# Belichter-Platinen.net
KiCad netlist of a schematic drawn in EAGLE
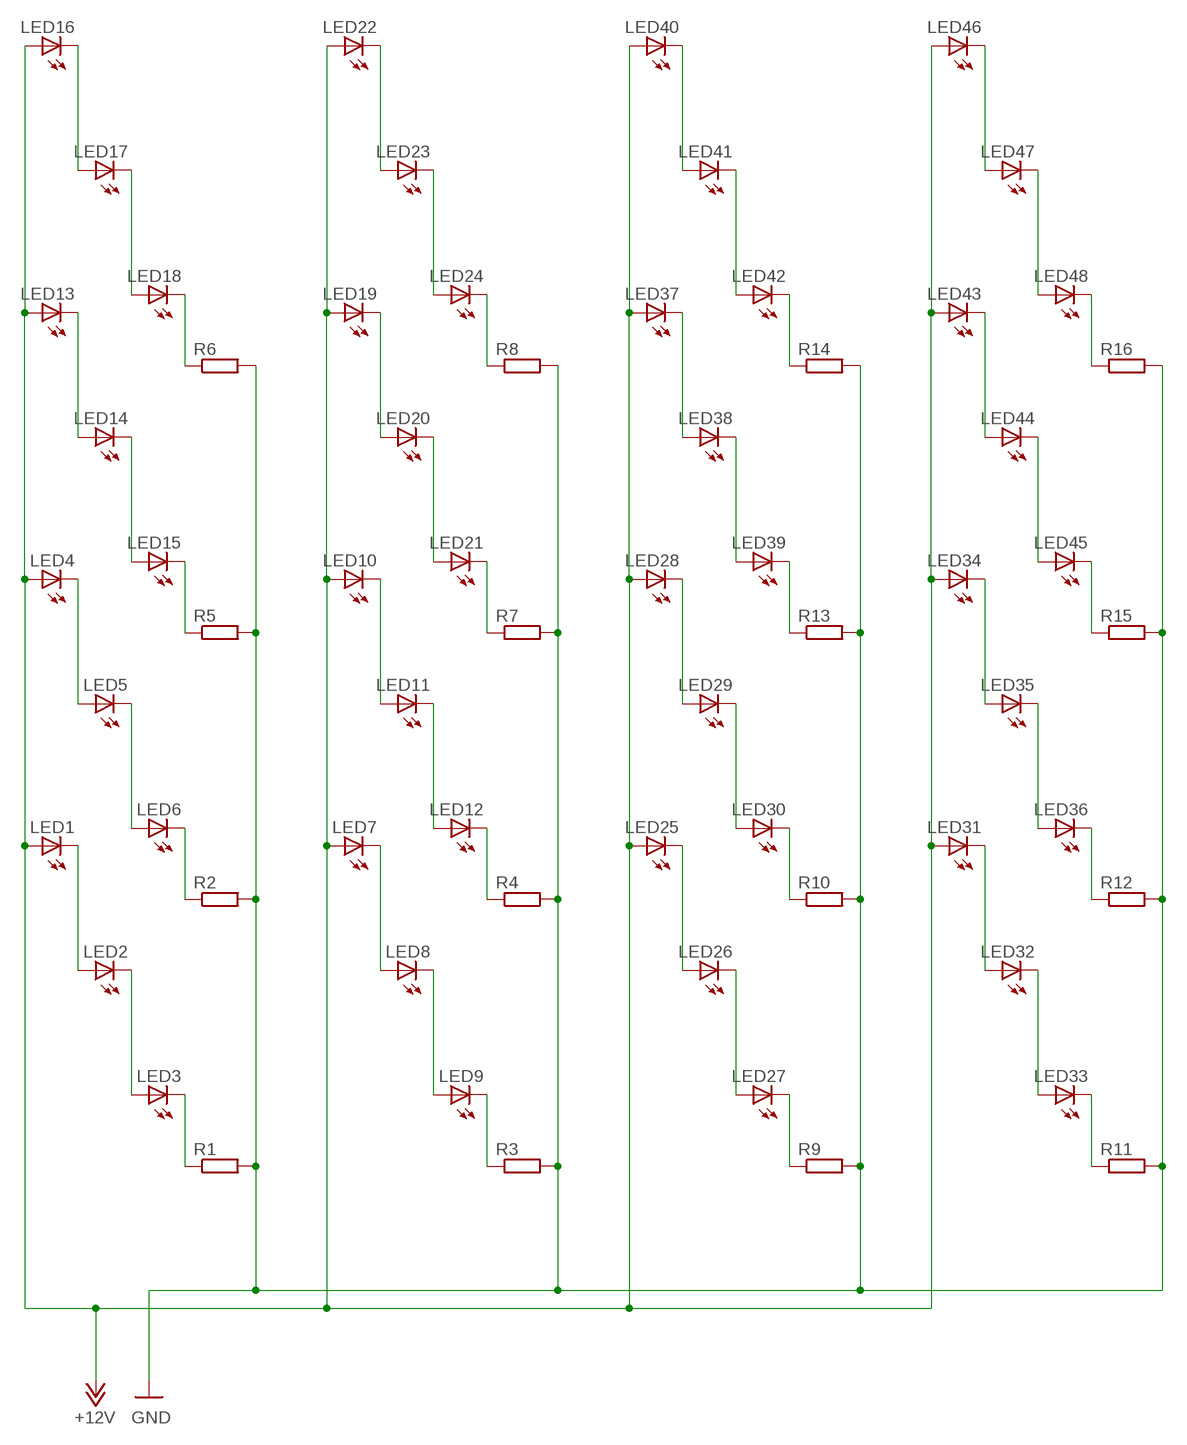
[diagram p0: schematic, sheet 1]

(export (version "E")
  (design (tool "Eeschema 10.0.6"))
  (components
    (comp (ref "LED1")
      (value "LED5MM")
      (footprint "eagle-import:LED5MM")
      (libsource (lib "eagle-import") (part "LED5MM"))
    )
    (comp (ref "LED2")
      (value "LED5MM")
      (footprint "eagle-import:LED5MM")
      (libsource (lib "eagle-import") (part "LED5MM"))
    )
    (comp (ref "LED3")
      (value "LED5MM")
      (footprint "eagle-import:LED5MM")
      (libsource (lib "eagle-import") (part "LED5MM"))
    )
    (comp (ref "LED4")
      (value "LED5MM")
      (footprint "eagle-import:LED5MM")
      (libsource (lib "eagle-import") (part "LED5MM"))
    )
    (comp (ref "LED5")
      (value "LED5MM")
      (footprint "eagle-import:LED5MM")
      (libsource (lib "eagle-import") (part "LED5MM"))
    )
    (comp (ref "LED6")
      (value "LED5MM")
      (footprint "eagle-import:LED5MM")
      (libsource (lib "eagle-import") (part "LED5MM"))
    )
    (comp (ref "LED7")
      (value "LED5MM")
      (footprint "eagle-import:LED5MM")
      (libsource (lib "eagle-import") (part "LED5MM"))
    )
    (comp (ref "LED8")
      (value "LED5MM")
      (footprint "eagle-import:LED5MM")
      (libsource (lib "eagle-import") (part "LED5MM"))
    )
    (comp (ref "LED9")
      (value "LED5MM")
      (footprint "eagle-import:LED5MM")
      (libsource (lib "eagle-import") (part "LED5MM"))
    )
    (comp (ref "LED10")
      (value "LED5MM")
      (footprint "eagle-import:LED5MM")
      (libsource (lib "eagle-import") (part "LED5MM"))
    )
    (comp (ref "LED11")
      (value "LED5MM")
      (footprint "eagle-import:LED5MM")
      (libsource (lib "eagle-import") (part "LED5MM"))
    )
    (comp (ref "LED12")
      (value "LED5MM")
      (footprint "eagle-import:LED5MM")
      (libsource (lib "eagle-import") (part "LED5MM"))
    )
    (comp (ref "LED13")
      (value "LED5MM")
      (footprint "eagle-import:LED5MM")
      (libsource (lib "eagle-import") (part "LED5MM"))
    )
    (comp (ref "LED14")
      (value "LED5MM")
      (footprint "eagle-import:LED5MM")
      (libsource (lib "eagle-import") (part "LED5MM"))
    )
    (comp (ref "LED15")
      (value "LED5MM")
      (footprint "eagle-import:LED5MM")
      (libsource (lib "eagle-import") (part "LED5MM"))
    )
    (comp (ref "LED16")
      (value "LED5MM")
      (footprint "eagle-import:LED5MM")
      (libsource (lib "eagle-import") (part "LED5MM"))
    )
    (comp (ref "LED17")
      (value "LED5MM")
      (footprint "eagle-import:LED5MM")
      (libsource (lib "eagle-import") (part "LED5MM"))
    )
    (comp (ref "LED18")
      (value "LED5MM")
      (footprint "eagle-import:LED5MM")
      (libsource (lib "eagle-import") (part "LED5MM"))
    )
    (comp (ref "LED19")
      (value "LED5MM")
      (footprint "eagle-import:LED5MM")
      (libsource (lib "eagle-import") (part "LED5MM"))
    )
    (comp (ref "LED20")
      (value "LED5MM")
      (footprint "eagle-import:LED5MM")
      (libsource (lib "eagle-import") (part "LED5MM"))
    )
    (comp (ref "LED21")
      (value "LED5MM")
      (footprint "eagle-import:LED5MM")
      (libsource (lib "eagle-import") (part "LED5MM"))
    )
    (comp (ref "LED22")
      (value "LED5MM")
      (footprint "eagle-import:LED5MM")
      (libsource (lib "eagle-import") (part "LED5MM"))
    )
    (comp (ref "LED23")
      (value "LED5MM")
      (footprint "eagle-import:LED5MM")
      (libsource (lib "eagle-import") (part "LED5MM"))
    )
    (comp (ref "LED24")
      (value "LED5MM")
      (footprint "eagle-import:LED5MM")
      (libsource (lib "eagle-import") (part "LED5MM"))
    )
    (comp (ref "LED25")
      (value "LED5MM")
      (footprint "eagle-import:LED5MM")
      (libsource (lib "eagle-import") (part "LED5MM"))
    )
    (comp (ref "LED26")
      (value "LED5MM")
      (footprint "eagle-import:LED5MM")
      (libsource (lib "eagle-import") (part "LED5MM"))
    )
    (comp (ref "LED27")
      (value "LED5MM")
      (footprint "eagle-import:LED5MM")
      (libsource (lib "eagle-import") (part "LED5MM"))
    )
    (comp (ref "LED28")
      (value "LED5MM")
      (footprint "eagle-import:LED5MM")
      (libsource (lib "eagle-import") (part "LED5MM"))
    )
    (comp (ref "LED29")
      (value "LED5MM")
      (footprint "eagle-import:LED5MM")
      (libsource (lib "eagle-import") (part "LED5MM"))
    )
    (comp (ref "LED30")
      (value "LED5MM")
      (footprint "eagle-import:LED5MM")
      (libsource (lib "eagle-import") (part "LED5MM"))
    )
    (comp (ref "LED31")
      (value "LED5MM")
      (footprint "eagle-import:LED5MM")
      (libsource (lib "eagle-import") (part "LED5MM"))
    )
    (comp (ref "LED32")
      (value "LED5MM")
      (footprint "eagle-import:LED5MM")
      (libsource (lib "eagle-import") (part "LED5MM"))
    )
    (comp (ref "LED33")
      (value "LED5MM")
      (footprint "eagle-import:LED5MM")
      (libsource (lib "eagle-import") (part "LED5MM"))
    )
    (comp (ref "LED34")
      (value "LED5MM")
      (footprint "eagle-import:LED5MM")
      (libsource (lib "eagle-import") (part "LED5MM"))
    )
    (comp (ref "LED35")
      (value "LED5MM")
      (footprint "eagle-import:LED5MM")
      (libsource (lib "eagle-import") (part "LED5MM"))
    )
    (comp (ref "LED36")
      (value "LED5MM")
      (footprint "eagle-import:LED5MM")
      (libsource (lib "eagle-import") (part "LED5MM"))
    )
    (comp (ref "LED37")
      (value "LED5MM")
      (footprint "eagle-import:LED5MM")
      (libsource (lib "eagle-import") (part "LED5MM"))
    )
    (comp (ref "LED38")
      (value "LED5MM")
      (footprint "eagle-import:LED5MM")
      (libsource (lib "eagle-import") (part "LED5MM"))
    )
    (comp (ref "LED39")
      (value "LED5MM")
      (footprint "eagle-import:LED5MM")
      (libsource (lib "eagle-import") (part "LED5MM"))
    )
    (comp (ref "LED40")
      (value "LED5MM")
      (footprint "eagle-import:LED5MM")
      (libsource (lib "eagle-import") (part "LED5MM"))
    )
    (comp (ref "LED41")
      (value "LED5MM")
      (footprint "eagle-import:LED5MM")
      (libsource (lib "eagle-import") (part "LED5MM"))
    )
    (comp (ref "LED42")
      (value "LED5MM")
      (footprint "eagle-import:LED5MM")
      (libsource (lib "eagle-import") (part "LED5MM"))
    )
    (comp (ref "LED43")
      (value "LED5MM")
      (footprint "eagle-import:LED5MM")
      (libsource (lib "eagle-import") (part "LED5MM"))
    )
    (comp (ref "LED44")
      (value "LED5MM")
      (footprint "eagle-import:LED5MM")
      (libsource (lib "eagle-import") (part "LED5MM"))
    )
    (comp (ref "LED45")
      (value "LED5MM")
      (footprint "eagle-import:LED5MM")
      (libsource (lib "eagle-import") (part "LED5MM"))
    )
    (comp (ref "LED46")
      (value "LED5MM")
      (footprint "eagle-import:LED5MM")
      (libsource (lib "eagle-import") (part "LED5MM"))
    )
    (comp (ref "LED47")
      (value "LED5MM")
      (footprint "eagle-import:LED5MM")
      (libsource (lib "eagle-import") (part "LED5MM"))
    )
    (comp (ref "LED48")
      (value "LED5MM")
      (footprint "eagle-import:LED5MM")
      (libsource (lib "eagle-import") (part "LED5MM"))
    )
    (comp (ref "R1")
      (value "R-EU_0207/10")
      (footprint "eagle-import:0207_10")
      (libsource (lib "eagle-import") (part "R-EU_0207/10"))
    )
    (comp (ref "R2")
      (value "R-EU_0207/10")
      (footprint "eagle-import:0207_10")
      (libsource (lib "eagle-import") (part "R-EU_0207/10"))
    )
    (comp (ref "R3")
      (value "R-EU_0207/10")
      (footprint "eagle-import:0207_10")
      (libsource (lib "eagle-import") (part "R-EU_0207/10"))
    )
    (comp (ref "R4")
      (value "R-EU_0207/10")
      (footprint "eagle-import:0207_10")
      (libsource (lib "eagle-import") (part "R-EU_0207/10"))
    )
    (comp (ref "R5")
      (value "R-EU_0207/10")
      (footprint "eagle-import:0207_10")
      (libsource (lib "eagle-import") (part "R-EU_0207/10"))
    )
    (comp (ref "R6")
      (value "R-EU_0207/10")
      (footprint "eagle-import:0207_10")
      (libsource (lib "eagle-import") (part "R-EU_0207/10"))
    )
    (comp (ref "R7")
      (value "R-EU_0207/10")
      (footprint "eagle-import:0207_10")
      (libsource (lib "eagle-import") (part "R-EU_0207/10"))
    )
    (comp (ref "R8")
      (value "R-EU_0207/10")
      (footprint "eagle-import:0207_10")
      (libsource (lib "eagle-import") (part "R-EU_0207/10"))
    )
    (comp (ref "R9")
      (value "R-EU_0207/10")
      (footprint "eagle-import:0207_10")
      (libsource (lib "eagle-import") (part "R-EU_0207/10"))
    )
    (comp (ref "R10")
      (value "R-EU_0207/10")
      (footprint "eagle-import:0207_10")
      (libsource (lib "eagle-import") (part "R-EU_0207/10"))
    )
    (comp (ref "R11")
      (value "R-EU_0207/10")
      (footprint "eagle-import:0207_10")
      (libsource (lib "eagle-import") (part "R-EU_0207/10"))
    )
    (comp (ref "R12")
      (value "R-EU_0207/10")
      (footprint "eagle-import:0207_10")
      (libsource (lib "eagle-import") (part "R-EU_0207/10"))
    )
    (comp (ref "R13")
      (value "R-EU_0207/10")
      (footprint "eagle-import:0207_10")
      (libsource (lib "eagle-import") (part "R-EU_0207/10"))
    )
    (comp (ref "R14")
      (value "R-EU_0207/10")
      (footprint "eagle-import:0207_10")
      (libsource (lib "eagle-import") (part "R-EU_0207/10"))
    )
    (comp (ref "R15")
      (value "R-EU_0207/10")
      (footprint "eagle-import:0207_10")
      (libsource (lib "eagle-import") (part "R-EU_0207/10"))
    )
    (comp (ref "R16")
      (value "R-EU_0207/10")
      (footprint "eagle-import:0207_10")
      (libsource (lib "eagle-import") (part "R-EU_0207/10"))
    )
  )
  (nets
    (net (code "1") (name "+12V") (class "Default")
      (node (ref "LED1") (pin "A") (pinfunction "A_A") (pintype "passive"))
      (node (ref "LED10") (pin "A") (pinfunction "A_A") (pintype "passive"))
      (node (ref "LED13") (pin "A") (pinfunction "A_A") (pintype "passive"))
      (node (ref "LED16") (pin "A") (pinfunction "A_A") (pintype "passive"))
      (node (ref "LED19") (pin "A") (pinfunction "A_A") (pintype "passive"))
      (node (ref "LED22") (pin "A") (pinfunction "A_A") (pintype "passive"))
      (node (ref "LED25") (pin "A") (pinfunction "A_A") (pintype "passive"))
      (node (ref "LED28") (pin "A") (pinfunction "A_A") (pintype "passive"))
      (node (ref "LED31") (pin "A") (pinfunction "A_A") (pintype "passive"))
      (node (ref "LED34") (pin "A") (pinfunction "A_A") (pintype "passive"))
      (node (ref "LED37") (pin "A") (pinfunction "A_A") (pintype "passive"))
      (node (ref "LED4") (pin "A") (pinfunction "A_A") (pintype "passive"))
      (node (ref "LED40") (pin "A") (pinfunction "A_A") (pintype "passive"))
      (node (ref "LED43") (pin "A") (pinfunction "A_A") (pintype "passive"))
      (node (ref "LED46") (pin "A") (pinfunction "A_A") (pintype "passive"))
      (node (ref "LED7") (pin "A") (pinfunction "A_A") (pintype "passive"))
    )
    (net (code "2") (name "GND") (class "Default")
      (node (ref "R1") (pin "2") (pinfunction "2_2") (pintype "passive"))
      (node (ref "R10") (pin "2") (pinfunction "2_2") (pintype "passive"))
      (node (ref "R11") (pin "2") (pinfunction "2_2") (pintype "passive"))
      (node (ref "R12") (pin "2") (pinfunction "2_2") (pintype "passive"))
      (node (ref "R13") (pin "2") (pinfunction "2_2") (pintype "passive"))
      (node (ref "R14") (pin "2") (pinfunction "2_2") (pintype "passive"))
      (node (ref "R15") (pin "2") (pinfunction "2_2") (pintype "passive"))
      (node (ref "R16") (pin "2") (pinfunction "2_2") (pintype "passive"))
      (node (ref "R2") (pin "2") (pinfunction "2_2") (pintype "passive"))
      (node (ref "R3") (pin "2") (pinfunction "2_2") (pintype "passive"))
      (node (ref "R4") (pin "2") (pinfunction "2_2") (pintype "passive"))
      (node (ref "R5") (pin "2") (pinfunction "2_2") (pintype "passive"))
      (node (ref "R6") (pin "2") (pinfunction "2_2") (pintype "passive"))
      (node (ref "R7") (pin "2") (pinfunction "2_2") (pintype "passive"))
      (node (ref "R8") (pin "2") (pinfunction "2_2") (pintype "passive"))
      (node (ref "R9") (pin "2") (pinfunction "2_2") (pintype "passive"))
    )
    (net (code "3") (name "Net-(LED1-C)") (class "Default")
      (node (ref "LED1") (pin "K") (pinfunction "C_K") (pintype "passive"))
      (node (ref "LED2") (pin "A") (pinfunction "A_A") (pintype "passive"))
    )
    (net (code "4") (name "Net-(LED2-C)") (class "Default")
      (node (ref "LED2") (pin "K") (pinfunction "C_K") (pintype "passive"))
      (node (ref "LED3") (pin "A") (pinfunction "A_A") (pintype "passive"))
    )
    (net (code "5") (name "Net-(LED3-C)") (class "Default")
      (node (ref "LED3") (pin "K") (pinfunction "C_K") (pintype "passive"))
      (node (ref "R1") (pin "1") (pinfunction "1_1") (pintype "passive"))
    )
    (net (code "6") (name "Net-(LED4-C)") (class "Default")
      (node (ref "LED4") (pin "K") (pinfunction "C_K") (pintype "passive"))
      (node (ref "LED5") (pin "A") (pinfunction "A_A") (pintype "passive"))
    )
    (net (code "7") (name "Net-(LED5-C)") (class "Default")
      (node (ref "LED5") (pin "K") (pinfunction "C_K") (pintype "passive"))
      (node (ref "LED6") (pin "A") (pinfunction "A_A") (pintype "passive"))
    )
    (net (code "8") (name "Net-(LED6-C)") (class "Default")
      (node (ref "LED6") (pin "K") (pinfunction "C_K") (pintype "passive"))
      (node (ref "R2") (pin "1") (pinfunction "1_1") (pintype "passive"))
    )
    (net (code "9") (name "Net-(LED7-C)") (class "Default")
      (node (ref "LED7") (pin "K") (pinfunction "C_K") (pintype "passive"))
      (node (ref "LED8") (pin "A") (pinfunction "A_A") (pintype "passive"))
    )
    (net (code "10") (name "Net-(LED8-C)") (class "Default")
      (node (ref "LED8") (pin "K") (pinfunction "C_K") (pintype "passive"))
      (node (ref "LED9") (pin "A") (pinfunction "A_A") (pintype "passive"))
    )
    (net (code "11") (name "Net-(LED9-C)") (class "Default")
      (node (ref "LED9") (pin "K") (pinfunction "C_K") (pintype "passive"))
      (node (ref "R3") (pin "1") (pinfunction "1_1") (pintype "passive"))
    )
    (net (code "12") (name "Net-(LED10-C)") (class "Default")
      (node (ref "LED10") (pin "K") (pinfunction "C_K") (pintype "passive"))
      (node (ref "LED11") (pin "A") (pinfunction "A_A") (pintype "passive"))
    )
    (net (code "13") (name "Net-(LED11-C)") (class "Default")
      (node (ref "LED11") (pin "K") (pinfunction "C_K") (pintype "passive"))
      (node (ref "LED12") (pin "A") (pinfunction "A_A") (pintype "passive"))
    )
    (net (code "14") (name "Net-(LED12-C)") (class "Default")
      (node (ref "LED12") (pin "K") (pinfunction "C_K") (pintype "passive"))
      (node (ref "R4") (pin "1") (pinfunction "1_1") (pintype "passive"))
    )
    (net (code "15") (name "Net-(LED13-C)") (class "Default")
      (node (ref "LED13") (pin "K") (pinfunction "C_K") (pintype "passive"))
      (node (ref "LED14") (pin "A") (pinfunction "A_A") (pintype "passive"))
    )
    (net (code "16") (name "Net-(LED14-C)") (class "Default")
      (node (ref "LED14") (pin "K") (pinfunction "C_K") (pintype "passive"))
      (node (ref "LED15") (pin "A") (pinfunction "A_A") (pintype "passive"))
    )
    (net (code "17") (name "Net-(LED15-C)") (class "Default")
      (node (ref "LED15") (pin "K") (pinfunction "C_K") (pintype "passive"))
      (node (ref "R5") (pin "1") (pinfunction "1_1") (pintype "passive"))
    )
    (net (code "18") (name "Net-(LED16-C)") (class "Default")
      (node (ref "LED16") (pin "K") (pinfunction "C_K") (pintype "passive"))
      (node (ref "LED17") (pin "A") (pinfunction "A_A") (pintype "passive"))
    )
    (net (code "19") (name "Net-(LED17-C)") (class "Default")
      (node (ref "LED17") (pin "K") (pinfunction "C_K") (pintype "passive"))
      (node (ref "LED18") (pin "A") (pinfunction "A_A") (pintype "passive"))
    )
    (net (code "20") (name "Net-(LED18-C)") (class "Default")
      (node (ref "LED18") (pin "K") (pinfunction "C_K") (pintype "passive"))
      (node (ref "R6") (pin "1") (pinfunction "1_1") (pintype "passive"))
    )
    (net (code "21") (name "Net-(LED19-C)") (class "Default")
      (node (ref "LED19") (pin "K") (pinfunction "C_K") (pintype "passive"))
      (node (ref "LED20") (pin "A") (pinfunction "A_A") (pintype "passive"))
    )
    (net (code "22") (name "Net-(LED20-C)") (class "Default")
      (node (ref "LED20") (pin "K") (pinfunction "C_K") (pintype "passive"))
      (node (ref "LED21") (pin "A") (pinfunction "A_A") (pintype "passive"))
    )
    (net (code "23") (name "Net-(LED21-C)") (class "Default")
      (node (ref "LED21") (pin "K") (pinfunction "C_K") (pintype "passive"))
      (node (ref "R7") (pin "1") (pinfunction "1_1") (pintype "passive"))
    )
    (net (code "24") (name "Net-(LED22-C)") (class "Default")
      (node (ref "LED22") (pin "K") (pinfunction "C_K") (pintype "passive"))
      (node (ref "LED23") (pin "A") (pinfunction "A_A") (pintype "passive"))
    )
    (net (code "25") (name "Net-(LED23-C)") (class "Default")
      (node (ref "LED23") (pin "K") (pinfunction "C_K") (pintype "passive"))
      (node (ref "LED24") (pin "A") (pinfunction "A_A") (pintype "passive"))
    )
    (net (code "26") (name "Net-(LED24-C)") (class "Default")
      (node (ref "LED24") (pin "K") (pinfunction "C_K") (pintype "passive"))
      (node (ref "R8") (pin "1") (pinfunction "1_1") (pintype "passive"))
    )
    (net (code "27") (name "Net-(LED25-C)") (class "Default")
      (node (ref "LED25") (pin "K") (pinfunction "C_K") (pintype "passive"))
      (node (ref "LED26") (pin "A") (pinfunction "A_A") (pintype "passive"))
    )
    (net (code "28") (name "Net-(LED26-C)") (class "Default")
      (node (ref "LED26") (pin "K") (pinfunction "C_K") (pintype "passive"))
      (node (ref "LED27") (pin "A") (pinfunction "A_A") (pintype "passive"))
    )
    (net (code "29") (name "Net-(LED27-C)") (class "Default")
      (node (ref "LED27") (pin "K") (pinfunction "C_K") (pintype "passive"))
      (node (ref "R9") (pin "1") (pinfunction "1_1") (pintype "passive"))
    )
    (net (code "30") (name "Net-(LED28-C)") (class "Default")
      (node (ref "LED28") (pin "K") (pinfunction "C_K") (pintype "passive"))
      (node (ref "LED29") (pin "A") (pinfunction "A_A") (pintype "passive"))
    )
    (net (code "31") (name "Net-(LED29-C)") (class "Default")
      (node (ref "LED29") (pin "K") (pinfunction "C_K") (pintype "passive"))
      (node (ref "LED30") (pin "A") (pinfunction "A_A") (pintype "passive"))
    )
    (net (code "32") (name "Net-(LED30-C)") (class "Default")
      (node (ref "LED30") (pin "K") (pinfunction "C_K") (pintype "passive"))
      (node (ref "R10") (pin "1") (pinfunction "1_1") (pintype "passive"))
    )
    (net (code "33") (name "Net-(LED31-C)") (class "Default")
      (node (ref "LED31") (pin "K") (pinfunction "C_K") (pintype "passive"))
      (node (ref "LED32") (pin "A") (pinfunction "A_A") (pintype "passive"))
    )
    (net (code "34") (name "Net-(LED32-C)") (class "Default")
      (node (ref "LED32") (pin "K") (pinfunction "C_K") (pintype "passive"))
      (node (ref "LED33") (pin "A") (pinfunction "A_A") (pintype "passive"))
    )
    (net (code "35") (name "Net-(LED33-C)") (class "Default")
      (node (ref "LED33") (pin "K") (pinfunction "C_K") (pintype "passive"))
      (node (ref "R11") (pin "1") (pinfunction "1_1") (pintype "passive"))
    )
    (net (code "36") (name "Net-(LED34-C)") (class "Default")
      (node (ref "LED34") (pin "K") (pinfunction "C_K") (pintype "passive"))
      (node (ref "LED35") (pin "A") (pinfunction "A_A") (pintype "passive"))
    )
    (net (code "37") (name "Net-(LED35-C)") (class "Default")
      (node (ref "LED35") (pin "K") (pinfunction "C_K") (pintype "passive"))
      (node (ref "LED36") (pin "A") (pinfunction "A_A") (pintype "passive"))
    )
    (net (code "38") (name "Net-(LED36-C)") (class "Default")
      (node (ref "LED36") (pin "K") (pinfunction "C_K") (pintype "passive"))
      (node (ref "R12") (pin "1") (pinfunction "1_1") (pintype "passive"))
    )
    (net (code "39") (name "Net-(LED37-C)") (class "Default")
      (node (ref "LED37") (pin "K") (pinfunction "C_K") (pintype "passive"))
      (node (ref "LED38") (pin "A") (pinfunction "A_A") (pintype "passive"))
    )
    (net (code "40") (name "Net-(LED38-C)") (class "Default")
      (node (ref "LED38") (pin "K") (pinfunction "C_K") (pintype "passive"))
      (node (ref "LED39") (pin "A") (pinfunction "A_A") (pintype "passive"))
    )
    (net (code "41") (name "Net-(LED39-C)") (class "Default")
      (node (ref "LED39") (pin "K") (pinfunction "C_K") (pintype "passive"))
      (node (ref "R13") (pin "1") (pinfunction "1_1") (pintype "passive"))
    )
    (net (code "42") (name "Net-(LED40-C)") (class "Default")
      (node (ref "LED40") (pin "K") (pinfunction "C_K") (pintype "passive"))
      (node (ref "LED41") (pin "A") (pinfunction "A_A") (pintype "passive"))
    )
    (net (code "43") (name "Net-(LED41-C)") (class "Default")
      (node (ref "LED41") (pin "K") (pinfunction "C_K") (pintype "passive"))
      (node (ref "LED42") (pin "A") (pinfunction "A_A") (pintype "passive"))
    )
    (net (code "44") (name "Net-(LED42-C)") (class "Default")
      (node (ref "LED42") (pin "K") (pinfunction "C_K") (pintype "passive"))
      (node (ref "R14") (pin "1") (pinfunction "1_1") (pintype "passive"))
    )
    (net (code "45") (name "Net-(LED43-C)") (class "Default")
      (node (ref "LED43") (pin "K") (pinfunction "C_K") (pintype "passive"))
      (node (ref "LED44") (pin "A") (pinfunction "A_A") (pintype "passive"))
    )
    (net (code "46") (name "Net-(LED44-C)") (class "Default")
      (node (ref "LED44") (pin "K") (pinfunction "C_K") (pintype "passive"))
      (node (ref "LED45") (pin "A") (pinfunction "A_A") (pintype "passive"))
    )
    (net (code "47") (name "Net-(LED45-C)") (class "Default")
      (node (ref "LED45") (pin "K") (pinfunction "C_K") (pintype "passive"))
      (node (ref "R15") (pin "1") (pinfunction "1_1") (pintype "passive"))
    )
    (net (code "48") (name "Net-(LED46-C)") (class "Default")
      (node (ref "LED46") (pin "K") (pinfunction "C_K") (pintype "passive"))
      (node (ref "LED47") (pin "A") (pinfunction "A_A") (pintype "passive"))
    )
    (net (code "49") (name "Net-(LED47-C)") (class "Default")
      (node (ref "LED47") (pin "K") (pinfunction "C_K") (pintype "passive"))
      (node (ref "LED48") (pin "A") (pinfunction "A_A") (pintype "passive"))
    )
    (net (code "50") (name "Net-(LED48-C)") (class "Default")
      (node (ref "LED48") (pin "K") (pinfunction "C_K") (pintype "passive"))
      (node (ref "R16") (pin "1") (pinfunction "1_1") (pintype "passive"))
    )
  )
)
